# current_mirror.net
KiCad netlist of a schematic drawn in Altium Designer
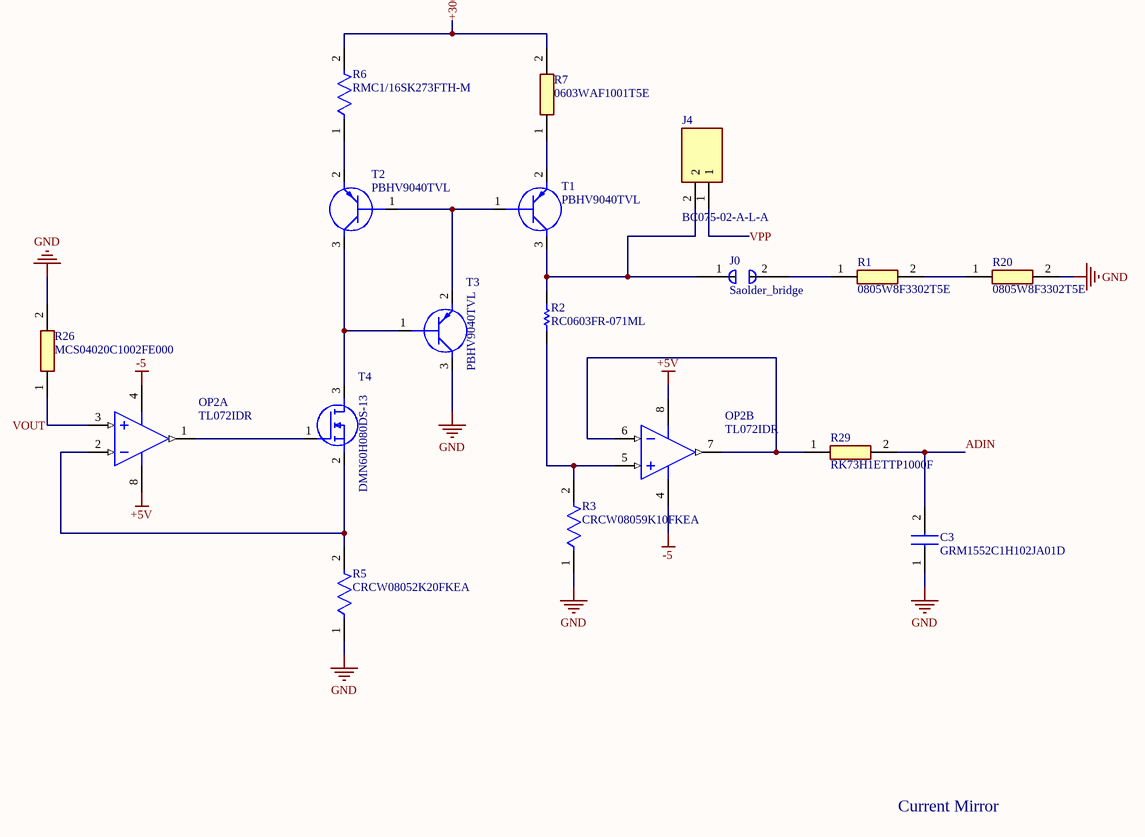
[diagram p0: current_mirror.SchDoc]

(export (version "E")
  (design (tool "Eeschema 10.0.6"))
  (components
    (comp (ref "C3")
      (value "GRM1552C1H102JA01D")
      (footprint "SamacSys:CAPC1005X70N")
      (description "Capacitor")
      (libsource (lib "*") (part "GRM1552C1H102JA01D"))
    )
    (comp (ref "J0")
      (value "Saolder_bridge")
      (footprint "Solder Bridge")
      (libsource (lib "solder_bridge") (part "Component_1"))
    )
    (comp (ref "J4")
      (value "BC075-02-A-L-A")
      (footprint "SamacSys:BC07502ALA")
      (description "Connector")
      (fields (field (name "MOUSER PART NUMBER") "640-BC075-02-A-L-A"))
      (libsource (lib "SamacSys") (part "BC075-02-A-L-A"))
    )
    (comp (ref "OP2")
      (value "TL072IDR")
      (footprint "D0008A_L")
      (fields (field (name "MANUFACTURER") "Texas Instruments"))
      (libsource (lib "Altium Content Vault") (part "TI-AMP-D6-2-8_D"))
    )
    (comp (ref "R1")
      (value "0805W8F3302T5E")
      (footprint "SamacSys:RESC2013X65N")
      (description "Resistor")
      (libsource (lib "*") (part "0805W8F3302T5E"))
    )
    (comp (ref "R2")
      (value "RC0603FR-071ML")
      (footprint "RESC1608X55X25LL10T15")
      (description "Chip Resistor, 1 MOhm, +/- 1%, 100 mW, -55 to 155 degC, 0603 (1608 Metric), RoHS, Tape and Reel")
      (fields (field (name "TOLERANCE") "20%"))
      (libsource (lib "Altium Content Vault") (part "RES-2"))
    )
    (comp (ref "R3")
      (value "CRCW08059K10FKEA")
      (footprint "FP-CRCW0805-e3-IPC_C")
      (description "RES Thick Film, 9.1kΩ, 1%, 0.125W, 100ppm/°C, 0805")
      (fields (field (name "TOLERANCE") "1%"))
      (libsource (lib "Altium Content Vault") (part "1029c3af85768c4190bb7ad29bc67b5"))
    )
    (comp (ref "R5")
      (value "CRCW08052K20FKEA")
      (footprint "FP-CRCW0805-e3-IPC_B")
      (description "RES Thick Film, 2.2kΩ, 1%, 0.125W, 100ppm/°C, 0805")
      (fields (field (name "TOLERANCE") "1%"))
      (libsource (lib "Altium Content Vault") (part "1029c3af85768c4190bb7ad29bc67b5"))
    )
    (comp (ref "R6")
      (value "RMC1/16SK273FTH-M")
      (footprint "FP-CRCW0402-e3-IPC_A")
      (description "RES Thick Film, 27kΩ, 1%, 0.063W, 100ppm/°C, 0402")
      (fields (field (name "TOLERANCE") "1%"))
      (libsource (lib "Altium Content Vault") (part "1029c3af85768c4190bb7ad29bc67b5"))
    )
    (comp (ref "R7")
      (value "0603WAF1001T5E")
      (footprint "SamacSys:RESC1608X55N")
      (description "Resistor")
      (libsource (lib "*") (part "0603WAF1001T5E"))
    )
    (comp (ref "R20")
      (value "0805W8F3302T5E")
      (footprint "SamacSys:RESC2013X65N")
      (description "Resistor")
      (libsource (lib "*") (part "0805W8F3302T5E"))
    )
    (comp (ref "R26")
      (value "MCS04020C1002FE000")
      (footprint "SamacSys:RESC1005X37N")
      (description "Resistor")
      (fields (field (name "MOUSER PART NUMBER") "594-MCS04020C1002FE0"))
      (libsource (lib "*") (part "MCS04020C1002FE000"))
    )
    (comp (ref "R29")
      (value "RK73H1ETTP1000F")
      (footprint "SamacSys:RESC1005X40N")
      (description "Resistor")
      (fields (field (name "MOUSER PART NUMBER") "660-RK73H1ETTP1000F"))
      (libsource (lib "*") (part "RK73H1ETTP1000F"))
    )
    (comp (ref "T1")
      (value "PBHV9040TVL")
      (footprint "SamacSys:SOT95P230X110-3N")
      (description "Transistor BJT PNP")
      (fields (field (name "MOUSER PART NUMBER") "771-PBHV9040TVL"))
      (libsource (lib "*") (part "PBHV9040TVL"))
    )
    (comp (ref "T2")
      (value "PBHV9040TVL")
      (footprint "SamacSys:SOT95P230X110-3N")
      (description "Transistor BJT PNP")
      (fields (field (name "MOUSER PART NUMBER") "771-PBHV9040TVL"))
      (libsource (lib "*") (part "PBHV9040TVL"))
    )
    (comp (ref "T3")
      (value "PBHV9040TVL")
      (footprint "SamacSys:SOT95P230X110-3N")
      (description "Transistor BJT PNP")
      (fields (field (name "MOUSER PART NUMBER") "771-PBHV9040TVL"))
      (libsource (lib "*") (part "PBHV9040TVL"))
    )
    (comp (ref "T4")
      (value "DMN60H080DS-13")
      (footprint "SamacSys:SOT96P240X110-3N")
      (description "MOSFET (N-Channel)")
      (fields (field (name "MOUSER PART NUMBER") "621-DMN60H080DS-13"))
      (libsource (lib "*") (part "DMN60H080DS-13"))
    )
  )
  (nets
    (net (code "1") (name "+5V") (class "Default")
      (node (ref "OP2") (pin "8") (pinfunction "VCC+_8") (pintype "power_in"))
    )
    (net (code "2") (name "-5") (class "Default")
      (node (ref "OP2") (pin "4") (pinfunction "VCC-_4") (pintype "passive"))
    )
    (net (code "3") (name "/+300V") (class "Default")
      (node (ref "R6") (pin "2") (pinfunction "2_2") (pintype "passive"))
      (node (ref "R7") (pin "2") (pinfunction "2_2") (pintype "passive"))
    )
    (net (code "4") (name "/ADIN") (class "Default")
      (node (ref "C3") (pin "2") (pinfunction "2_2") (pintype "passive"))
      (node (ref "R29") (pin "2") (pinfunction "2_2") (pintype "passive"))
    )
    (net (code "5") (name "/VOUT") (class "Default")
      (node (ref "OP2") (pin "3") (pinfunction "IN1+_3") (pintype "input"))
      (node (ref "R26") (pin "1") (pinfunction "1_1") (pintype "passive"))
    )
    (net (code "6") (name "/VPP") (class "Default")
      (node (ref "J4") (pin "1") (pinfunction "1_1") (pintype "passive"))
    )
    (net (code "7") (name "GND") (class "Default")
      (node (ref "C3") (pin "1") (pinfunction "1_1") (pintype "passive"))
      (node (ref "R20") (pin "2") (pinfunction "2_2") (pintype "passive"))
      (node (ref "R26") (pin "2") (pinfunction "2_2") (pintype "passive"))
      (node (ref "R3") (pin "1") (pinfunction "1_1") (pintype "passive"))
      (node (ref "R5") (pin "1") (pinfunction "1_1") (pintype "passive"))
      (node (ref "T3") (pin "3") (pinfunction "C_3") (pintype "passive"))
    )
    (net (code "8") (name "Net-(J0-Pad2)") (class "Default")
      (node (ref "J0") (pin "2") (pinfunction "2_2") (pintype "passive"))
      (node (ref "R1") (pin "1") (pinfunction "1_1") (pintype "passive"))
    )
    (net (code "9") (name "Net-(OP2A-IN1-)") (class "Default")
      (node (ref "OP2") (pin "2") (pinfunction "IN1-_2") (pintype "input"))
      (node (ref "R5") (pin "2") (pinfunction "2_2") (pintype "passive"))
      (node (ref "T4") (pin "2") (pinfunction "S_2") (pintype "passive"))
    )
    (net (code "10") (name "Net-(OP2A-OUT1)") (class "Default")
      (node (ref "OP2") (pin "1") (pinfunction "OUT1_1") (pintype "output"))
      (node (ref "T4") (pin "1") (pinfunction "G_1") (pintype "passive"))
    )
    (net (code "11") (name "Net-(OP2B-IN2+)") (class "Default")
      (node (ref "OP2") (pin "5") (pinfunction "IN2+_5") (pintype "input"))
      (node (ref "R2") (pin "1") (pinfunction "1_1") (pintype "passive"))
      (node (ref "R3") (pin "2") (pinfunction "2_2") (pintype "passive"))
    )
    (net (code "12") (name "Net-(OP2B-IN2-)") (class "Default")
      (node (ref "OP2") (pin "6") (pinfunction "IN2-_6") (pintype "input"))
      (node (ref "OP2") (pin "7") (pinfunction "OUT2_7") (pintype "output"))
      (node (ref "R29") (pin "1") (pinfunction "1_1") (pintype "passive"))
    )
    (net (code "13") (name "Net-(R1-Pad2)") (class "Default")
      (node (ref "R1") (pin "2") (pinfunction "2_2") (pintype "passive"))
      (node (ref "R20") (pin "1") (pinfunction "1_1") (pintype "passive"))
    )
    (net (code "14") (name "Net-(T1-B)") (class "Default")
      (node (ref "T1") (pin "1") (pinfunction "B_1") (pintype "passive"))
      (node (ref "T2") (pin "1") (pinfunction "B_1") (pintype "passive"))
      (node (ref "T3") (pin "2") (pinfunction "E_2") (pintype "passive"))
    )
    (net (code "15") (name "Net-(T1-C)") (class "Default")
      (node (ref "J0") (pin "1") (pinfunction "1_1") (pintype "passive"))
      (node (ref "J4") (pin "2") (pinfunction "2_2") (pintype "passive"))
      (node (ref "R2") (pin "2") (pinfunction "2_2") (pintype "passive"))
      (node (ref "T1") (pin "3") (pinfunction "C_3") (pintype "passive"))
    )
    (net (code "16") (name "Net-(T1-E)") (class "Default")
      (node (ref "R7") (pin "1") (pinfunction "1_1") (pintype "passive"))
      (node (ref "T1") (pin "2") (pinfunction "E_2") (pintype "passive"))
    )
    (net (code "17") (name "Net-(T2-C)") (class "Default")
      (node (ref "T2") (pin "3") (pinfunction "C_3") (pintype "passive"))
      (node (ref "T3") (pin "1") (pinfunction "B_1") (pintype "passive"))
      (node (ref "T4") (pin "3") (pinfunction "D_3") (pintype "passive"))
    )
    (net (code "18") (name "Net-(T2-E)") (class "Default")
      (node (ref "R6") (pin "1") (pinfunction "1_1") (pintype "passive"))
      (node (ref "T2") (pin "2") (pinfunction "E_2") (pintype "passive"))
    )
  )
)
